# R1250GSA_Foglamp_Swith.net
KiCad netlist of a schematic drawn in Altium Designer
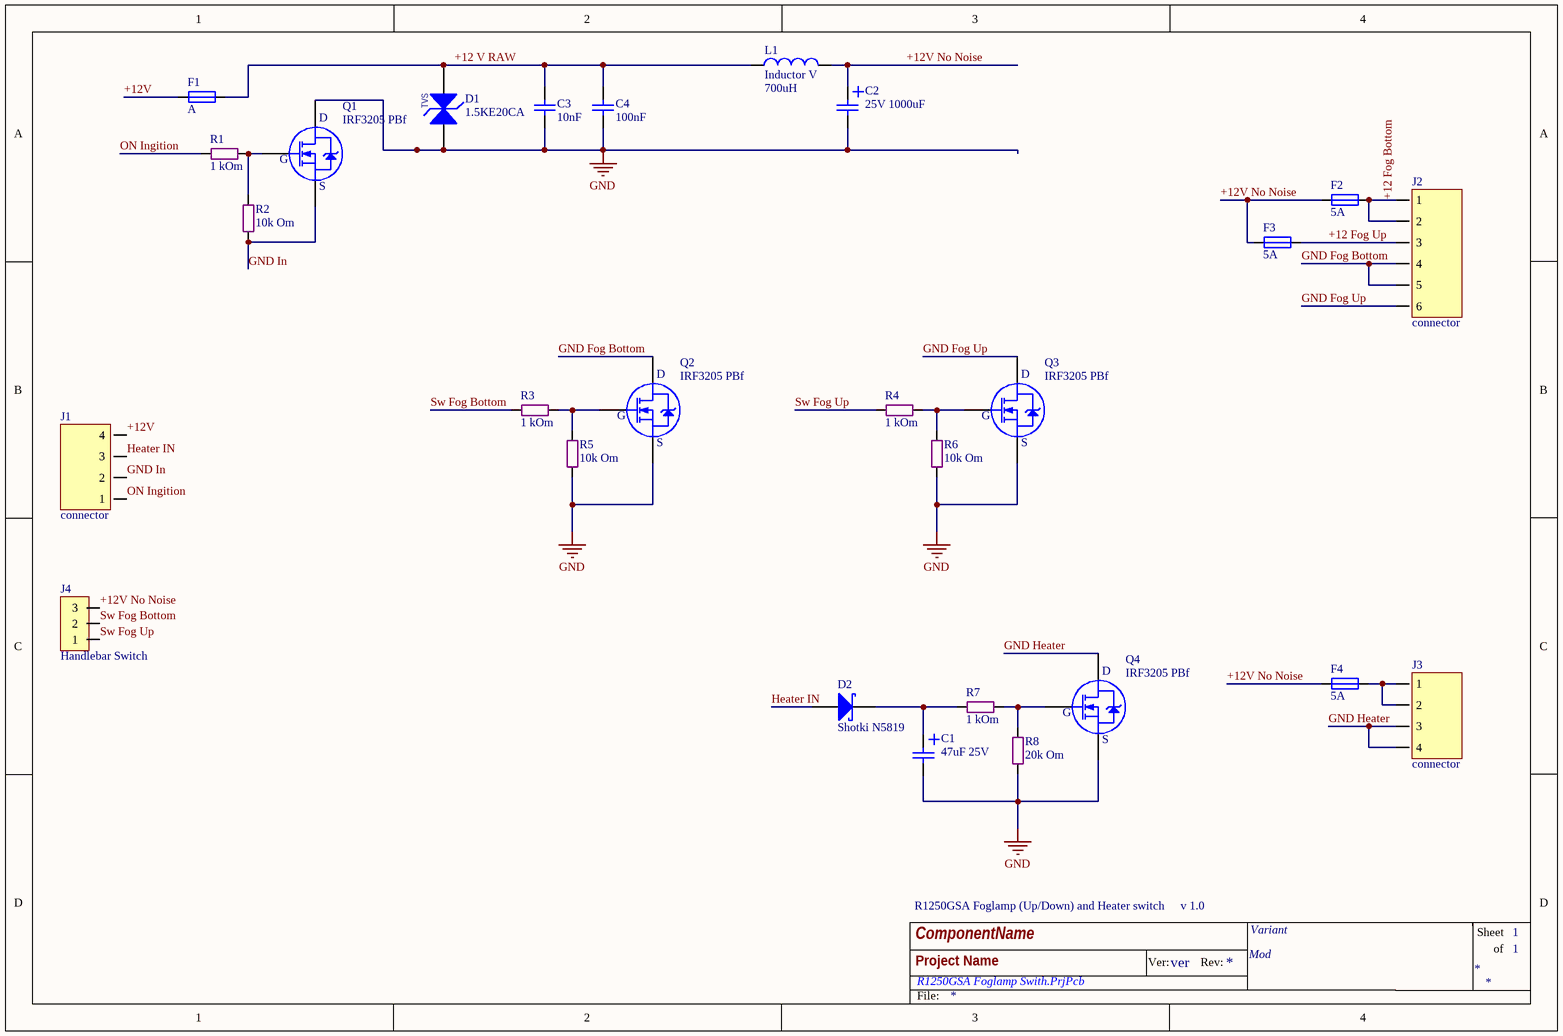
[diagram p0: R1250GSA Foglamp Swith.SchDoc]

(export (version "E")
  (design (tool "Eeschema 10.0.6"))
  (components
    (comp (ref "C1")
      (value "47uF 25V")
      (footprint "Capacitor:Cap E p2mm D6.5xH11")
      (description "Capacitor")
      (libsource (lib "Capacitor") (part "Cap Elecrolitic"))
    )
    (comp (ref "C2")
      (value "25V 1000uF")
      (footprint "Capacitor:Cap E p5.08mm D10.2mm (3p)")
      (description "Capacitor")
      (libsource (lib "Capacitor") (part "Cap E 1000mF x 25V"))
    )
    (comp (ref "C3")
      (value "10nF")
      (footprint "Capacitor:SMD 1206 (3216)")
      (description "Capacitor")
      (libsource (lib "Capacitor") (part "Cap Ceramic SMD (All)"))
    )
    (comp (ref "C4")
      (value "100nF")
      (footprint "Capacitor:SMD 1206 (3216)")
      (description "Capacitor")
      (libsource (lib "Capacitor") (part "Cap Ceramic SMD (All)"))
    )
    (comp (ref "D1")
      (value "1.5KE20CA")
      (footprint "Diodes:TVS diode DO-201 V")
      (description "1500W Transil (TVS Diode)")
      (libsource (lib "Diodes") (part "TVS 1.5KE20CA"))
    )
    (comp (ref "D2")
      (value "Shotki N5819")
      (footprint "Diodes:Diode DO-41")
      (description "Shotki  Diode")
      (libsource (lib "Diodes") (part "D Shotki All"))
    )
    (comp (ref "F1")
      (value "A")
      (footprint "PassiveComponents:Fuse RGE1100")
      (description "Round fuse")
      (libsource (lib "PassiveComponents") (part "Fuse"))
    )
    (comp (ref "F2")
      (value "5A")
      (footprint "PassiveComponents:Fuse RGE1100")
      (description "Round fuse")
      (libsource (lib "PassiveComponents") (part "Fuse"))
    )
    (comp (ref "F3")
      (value "5A")
      (footprint "PassiveComponents:Fuse RGE1100")
      (description "Round fuse")
      (libsource (lib "PassiveComponents") (part "Fuse"))
    )
    (comp (ref "F4")
      (value "5A")
      (footprint "PassiveComponents:Fuse RGE1100")
      (description "Round fuse")
      (libsource (lib "PassiveComponents") (part "Fuse"))
    )
    (comp (ref "J1")
      (value "connector")
      (footprint "Connector:Molex Mini-Fit Jr - 4Pin V")
      (description "Right, Dbl line, Female")
      (libsource (lib "") (part "Molex Mini-Fit Jr - 4 pin_1"))
    )
    (comp (ref "J2")
      (value "connector")
      (footprint "Connector:Molex Mini-Fit Jr - 6Pin V")
      (description "Right, Dbl line, Female")
      (libsource (lib "Connector") (part "Molex Mini-Fit Jr - 6 pin"))
    )
    (comp (ref "J3")
      (value "connector")
      (footprint "Connector:Molex Mini-Fit Jr - 4Pin V")
      (description "Right, Dbl line, Female")
      (libsource (lib "Connector") (part "Molex Mini-Fit Jr - 4 pin"))
    )
    (comp (ref "J4")
      (value "Handlebar Switch")
      (footprint "Connector:WF-3")
      (description "Standart Fan MB's Connector")
      (libsource (lib "Connector") (part "WF-3"))
    )
    (comp (ref "L1")
      (value "Inductor V")
      (footprint "Transformers:Toroid V D14-W6")
      (description "Inductor Vertical")
      (fields (field (name "ALTIUM_VALUE") "700uH") (field (name "PUBLISHER") "Altium Limited"))
      (libsource (lib "Transformers") (part "Inductor V"))
    )
    (comp (ref "Q1")
      (value "IRF3205 PBf")
      (footprint "GeneralCases:TO220-2")
      (description "N-Channel 55V - 0.008Ω - 110A")
      (libsource (lib "Transistor") (part "IRF3205"))
    )
    (comp (ref "Q2")
      (value "IRF3205 PBf")
      (footprint "GeneralCases:TO220-2")
      (description "N-Channel 55V - 0.008Ω - 110A")
      (libsource (lib "Transistor") (part "IRF3205"))
    )
    (comp (ref "Q3")
      (value "IRF3205 PBf")
      (footprint "GeneralCases:TO220-2")
      (description "N-Channel 55V - 0.008Ω - 110A")
      (libsource (lib "Transistor") (part "IRF3205"))
    )
    (comp (ref "Q4")
      (value "IRF3205 PBf")
      (footprint "GeneralCases:TO220-2")
      (description "N-Channel 55V - 0.008Ω - 110A")
      (libsource (lib "Transistor") (part "IRF3205"))
    )
    (comp (ref "R1")
      (value "1 kOm")
      (footprint "PassiveComponents:SMD 0805 (2012)")
      (libsource (lib "PassiveComponents") (part "Res All Types"))
    )
    (comp (ref "R2")
      (value "10k Om")
      (footprint "PassiveComponents:SMD 0805 (2012)")
      (libsource (lib "PassiveComponents") (part "Res All Types"))
    )
    (comp (ref "R3")
      (value "1 kOm")
      (footprint "PassiveComponents:SMD 0805 (2012)")
      (libsource (lib "PassiveComponents") (part "Res All Types"))
    )
    (comp (ref "R4")
      (value "1 kOm")
      (footprint "PassiveComponents:SMD 0805 (2012)")
      (libsource (lib "PassiveComponents") (part "Res All Types"))
    )
    (comp (ref "R5")
      (value "10k Om")
      (footprint "PassiveComponents:SMD 0805 (2012)")
      (libsource (lib "PassiveComponents") (part "Res All Types"))
    )
    (comp (ref "R6")
      (value "10k Om")
      (footprint "PassiveComponents:SMD 0805 (2012)")
      (libsource (lib "PassiveComponents") (part "Res All Types"))
    )
    (comp (ref "R7")
      (value "1 kOm")
      (footprint "PassiveComponents:SMD 0805 (2012)")
      (libsource (lib "PassiveComponents") (part "Res All Types"))
    )
    (comp (ref "R8")
      (value "20k Om")
      (footprint "PassiveComponents:SMD 0805 (2012)")
      (libsource (lib "PassiveComponents") (part "Res All Types"))
    )
  )
  (nets
    (net (code "1") (name "/+12 Fog Bottom") (class "Default")
      (node (ref "F2") (pin "2") (pinfunction "2_2") (pintype "passive"))
      (node (ref "J2") (pin "1") (pinfunction "1_1") (pintype "passive"))
      (node (ref "J2") (pin "2") (pinfunction "2_2") (pintype "passive"))
    )
    (net (code "2") (name "/+12 Fog Up") (class "Default")
      (node (ref "F3") (pin "2") (pinfunction "2_2") (pintype "passive"))
      (node (ref "J2") (pin "3") (pinfunction "3_3") (pintype "passive"))
    )
    (net (code "3") (name "/+12 V RAW") (class "Default")
      (node (ref "C3") (pin "1") (pinfunction "1_1") (pintype "passive"))
      (node (ref "C4") (pin "1") (pinfunction "1_1") (pintype "passive"))
      (node (ref "D1") (pin "2") (pinfunction "2_2") (pintype "passive"))
      (node (ref "F1") (pin "2") (pinfunction "2_2") (pintype "passive"))
      (node (ref "L1") (pin "1") (pinfunction "1_1") (pintype "passive"))
    )
    (net (code "4") (name "/+12V") (class "Default")
      (node (ref "F1") (pin "1") (pinfunction "1_1") (pintype "passive"))
      (node (ref "J1") (pin "4") (pinfunction "4_4") (pintype "passive"))
    )
    (net (code "5") (name "/+12V No Noise") (class "Default")
      (node (ref "C2") (pin "1") (pinfunction "1_1") (pintype "passive"))
      (node (ref "F2") (pin "1") (pinfunction "1_1") (pintype "passive"))
      (node (ref "F3") (pin "1") (pinfunction "1_1") (pintype "passive"))
      (node (ref "F4") (pin "1") (pinfunction "1_1") (pintype "passive"))
      (node (ref "J4") (pin "3") (pinfunction "3_3") (pintype "passive"))
      (node (ref "L1") (pin "2") (pinfunction "2_2") (pintype "passive"))
    )
    (net (code "6") (name "/GND Fog Bottom") (class "Default")
      (node (ref "J2") (pin "4") (pinfunction "4_4") (pintype "passive"))
      (node (ref "J2") (pin "5") (pinfunction "5_5") (pintype "passive"))
      (node (ref "Q2") (pin "2") (pinfunction "D_2") (pintype "passive"))
    )
    (net (code "7") (name "/GND Fog Up") (class "Default")
      (node (ref "J2") (pin "6") (pinfunction "6_6") (pintype "passive"))
      (node (ref "Q3") (pin "2") (pinfunction "D_2") (pintype "passive"))
    )
    (net (code "8") (name "/GND Heater") (class "Default")
      (node (ref "J3") (pin "3") (pinfunction "3_3") (pintype "passive"))
      (node (ref "J3") (pin "4") (pinfunction "4_4") (pintype "passive"))
      (node (ref "Q4") (pin "2") (pinfunction "D_2") (pintype "passive"))
    )
    (net (code "9") (name "/GND In") (class "Default")
      (node (ref "J1") (pin "2") (pinfunction "2_2") (pintype "passive"))
      (node (ref "Q1") (pin "3") (pinfunction "S_3") (pintype "passive"))
      (node (ref "R2") (pin "1") (pinfunction "1_1") (pintype "passive"))
    )
    (net (code "10") (name "/Heater IN") (class "Default")
      (node (ref "D2") (pin "A") (pinfunction "A_A") (pintype "passive"))
      (node (ref "J1") (pin "3") (pinfunction "3_3") (pintype "passive"))
    )
    (net (code "11") (name "/ON Ingition") (class "Default")
      (node (ref "J1") (pin "1") (pinfunction "1_1") (pintype "passive"))
      (node (ref "R1") (pin "1") (pinfunction "1_1") (pintype "passive"))
    )
    (net (code "12") (name "/Sw Fog Bottom") (class "Default")
      (node (ref "J4") (pin "2") (pinfunction "2_2") (pintype "passive"))
      (node (ref "R3") (pin "1") (pinfunction "1_1") (pintype "passive"))
    )
    (net (code "13") (name "/Sw Fog Up") (class "Default")
      (node (ref "J4") (pin "1") (pinfunction "1_1") (pintype "passive"))
      (node (ref "R4") (pin "1") (pinfunction "1_1") (pintype "passive"))
    )
    (net (code "14") (name "GND") (class "Default")
      (node (ref "C1") (pin "2") (pinfunction "2_2") (pintype "passive"))
      (node (ref "C2") (pin "2") (pinfunction "2_2") (pintype "passive"))
      (node (ref "C3") (pin "2") (pinfunction "2_2") (pintype "passive"))
      (node (ref "C4") (pin "2") (pinfunction "2_2") (pintype "passive"))
      (node (ref "D1") (pin "1") (pinfunction "1_1") (pintype "passive"))
      (node (ref "Q1") (pin "2") (pinfunction "D_2") (pintype "passive"))
      (node (ref "Q2") (pin "3") (pinfunction "S_3") (pintype "passive"))
      (node (ref "Q3") (pin "3") (pinfunction "S_3") (pintype "passive"))
      (node (ref "Q4") (pin "3") (pinfunction "S_3") (pintype "passive"))
      (node (ref "R5") (pin "1") (pinfunction "1_1") (pintype "passive"))
      (node (ref "R6") (pin "1") (pinfunction "1_1") (pintype "passive"))
      (node (ref "R8") (pin "1") (pinfunction "1_1") (pintype "passive"))
    )
    (net (code "15") (name "Net-(C1-Pad1)") (class "Default")
      (node (ref "C1") (pin "1") (pinfunction "1_1") (pintype "passive"))
      (node (ref "D2") (pin "K") (pinfunction "K_K") (pintype "passive"))
      (node (ref "R7") (pin "1") (pinfunction "1_1") (pintype "passive"))
    )
    (net (code "16") (name "Net-(F4-Pad2)") (class "Default")
      (node (ref "F4") (pin "2") (pinfunction "2_2") (pintype "passive"))
      (node (ref "J3") (pin "1") (pinfunction "1_1") (pintype "passive"))
      (node (ref "J3") (pin "2") (pinfunction "2_2") (pintype "passive"))
    )
    (net (code "17") (name "Net-(Q1-G)") (class "Default")
      (node (ref "Q1") (pin "1") (pinfunction "G_1") (pintype "passive"))
      (node (ref "R1") (pin "2") (pinfunction "2_2") (pintype "passive"))
      (node (ref "R2") (pin "2") (pinfunction "2_2") (pintype "passive"))
    )
    (net (code "18") (name "Net-(Q2-G)") (class "Default")
      (node (ref "Q2") (pin "1") (pinfunction "G_1") (pintype "passive"))
      (node (ref "R3") (pin "2") (pinfunction "2_2") (pintype "passive"))
      (node (ref "R5") (pin "2") (pinfunction "2_2") (pintype "passive"))
    )
    (net (code "19") (name "Net-(Q3-G)") (class "Default")
      (node (ref "Q3") (pin "1") (pinfunction "G_1") (pintype "passive"))
      (node (ref "R4") (pin "2") (pinfunction "2_2") (pintype "passive"))
      (node (ref "R6") (pin "2") (pinfunction "2_2") (pintype "passive"))
    )
    (net (code "20") (name "Net-(Q4-G)") (class "Default")
      (node (ref "Q4") (pin "1") (pinfunction "G_1") (pintype "passive"))
      (node (ref "R7") (pin "2") (pinfunction "2_2") (pintype "passive"))
      (node (ref "R8") (pin "2") (pinfunction "2_2") (pintype "passive"))
    )
  )
)
